# ROBOTICARM.net
KiCad netlist of a schematic drawn in Altium Designer
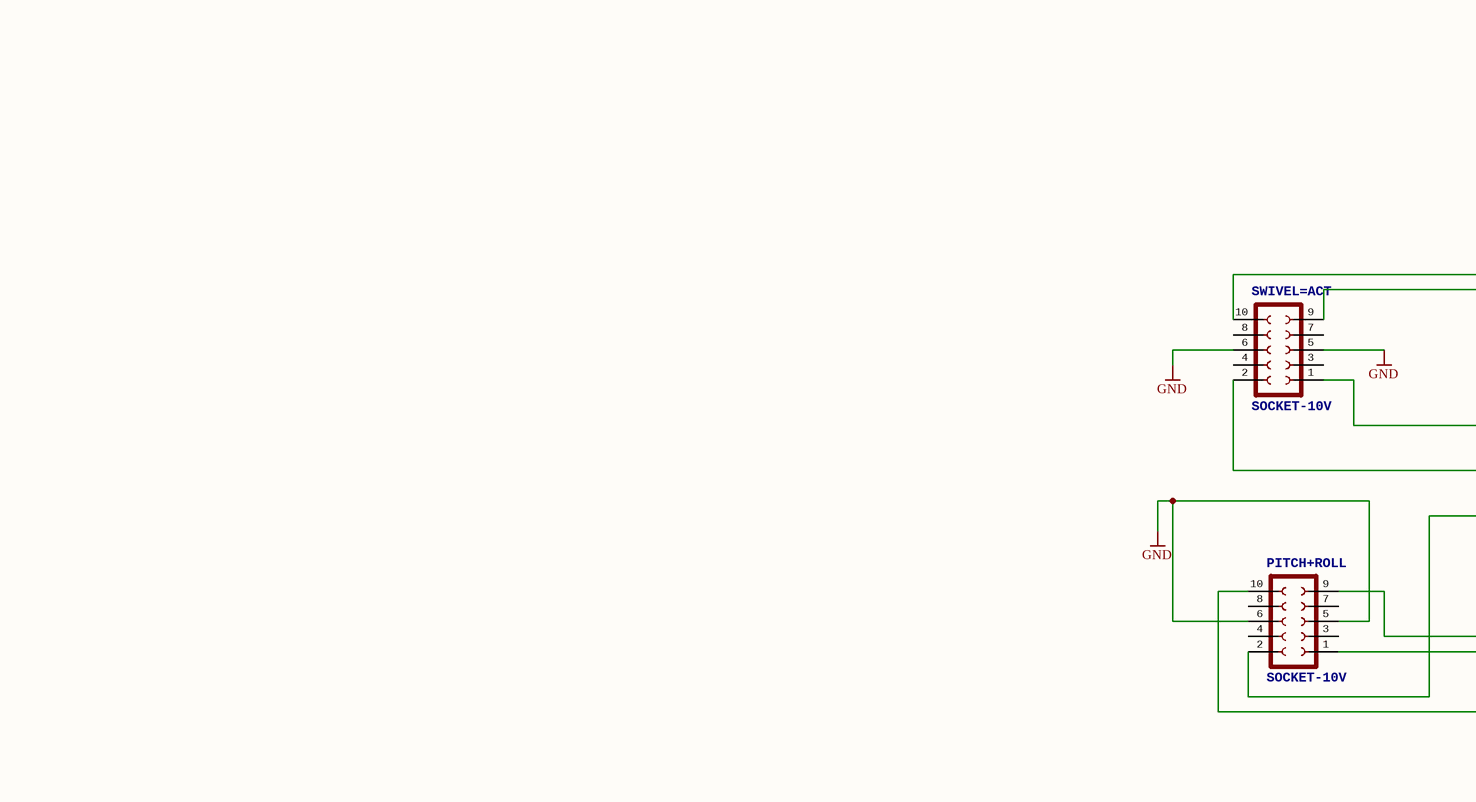
[diagram p0: ROBOTICARM.SchDoc, left]
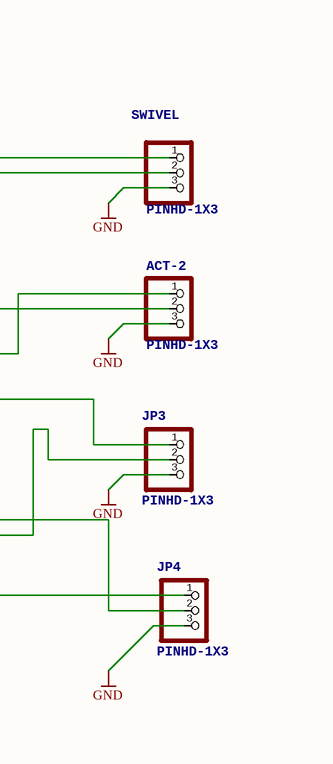
[diagram p1: ROBOTICARM.SchDoc, middle]

(export (version "E")
  (design (tool "Eeschema 10.0.6"))
  (components
    (comp (ref "ACT-2")
      (value "PINHD-1X3")
      (footprint "1X03")
      (description "PIN HEADER")
      (libsource (lib "pinhead") (part "PINHD-1X3"))
    )
    (comp (ref "JP3")
      (value "PINHD-1X3")
      (footprint "1X03")
      (description "PIN HEADER")
      (libsource (lib "pinhead") (part "PINHD-1X3"))
    )
    (comp (ref "JP4")
      (value "PINHD-1X3")
      (footprint "1X03")
      (description "PIN HEADER")
      (libsource (lib "pinhead") (part "PINHD-1X3"))
    )
    (comp (ref "MRM1")
      (value "MRM")
      (footprint "LOL")
      (fields (field (name "MRMLOGO") "MRM Logo"))
      (libsource (lib "MRM") (part "MRM"))
    )
    (comp (ref "PITCH+ROLL")
      (value "SOCKET-10V")
      (footprint "S10V")
      (description "10 pin PCB Socket (3m 85xx/51xx)")
      (libsource (lib "con-3m-skt-header") (part "SOCKET-10V"))
    )
    (comp (ref "SWIVEL")
      (value "PINHD-1X3")
      (footprint "1X03")
      (description "PIN HEADER")
      (libsource (lib "pinhead") (part "PINHD-1X3"))
    )
    (comp (ref "SWIVEL=ACT")
      (value "SOCKET-10V")
      (footprint "S10V")
      (description "10 pin PCB Socket (3m 85xx/51xx)")
      (libsource (lib "con-3m-skt-header") (part "SOCKET-10V"))
    )
  )
  (nets
    (net (code "1") (name "GND") (class "Default")
      (node (ref "ACT-2") (pin "3") (pinfunction "3_3") (pintype "passive"))
      (node (ref "JP3") (pin "3") (pinfunction "3_3") (pintype "passive"))
      (node (ref "JP4") (pin "3") (pinfunction "3_3") (pintype "passive"))
      (node (ref "PITCH+ROLL") (pin "5") (pinfunction "5_5") (pintype "passive"))
      (node (ref "PITCH+ROLL") (pin "6") (pinfunction "6_6") (pintype "passive"))
      (node (ref "SWIVEL") (pin "3") (pinfunction "3_3") (pintype "passive"))
      (node (ref "SWIVEL=ACT") (pin "5") (pinfunction "5_5") (pintype "passive"))
      (node (ref "SWIVEL=ACT") (pin "6") (pinfunction "6_6") (pintype "passive"))
    )
    (net (code "2") (name "Net-(ACT-2-Pad1)") (class "Default")
      (node (ref "ACT-2") (pin "1") (pinfunction "1_1") (pintype "passive"))
      (node (ref "SWIVEL=ACT") (pin "2") (pinfunction "2_2") (pintype "passive"))
    )
    (net (code "3") (name "Net-(ACT-2-Pad2)") (class "Default")
      (node (ref "ACT-2") (pin "2") (pinfunction "2_2") (pintype "passive"))
      (node (ref "SWIVEL=ACT") (pin "1") (pinfunction "1_1") (pintype "passive"))
    )
    (net (code "4") (name "Net-(JP3-Pad1)") (class "Default")
      (node (ref "JP3") (pin "1") (pinfunction "1_1") (pintype "passive"))
      (node (ref "PITCH+ROLL") (pin "2") (pinfunction "2_2") (pintype "passive"))
    )
    (net (code "5") (name "Net-(JP3-Pad2)") (class "Default")
      (node (ref "JP3") (pin "2") (pinfunction "2_2") (pintype "passive"))
      (node (ref "PITCH+ROLL") (pin "1") (pinfunction "1_1") (pintype "passive"))
    )
    (net (code "6") (name "Net-(JP4-Pad1)") (class "Default")
      (node (ref "JP4") (pin "1") (pinfunction "1_1") (pintype "passive"))
      (node (ref "PITCH+ROLL") (pin "10") (pinfunction "10_10") (pintype "passive"))
    )
    (net (code "7") (name "Net-(JP4-Pad2)") (class "Default")
      (node (ref "JP4") (pin "2") (pinfunction "2_2") (pintype "passive"))
      (node (ref "PITCH+ROLL") (pin "9") (pinfunction "9_9") (pintype "passive"))
    )
    (net (code "8") (name "Net-(SWIVEL-Pad1)") (class "Default")
      (node (ref "SWIVEL") (pin "1") (pinfunction "1_1") (pintype "passive"))
      (node (ref "SWIVEL=ACT") (pin "10") (pinfunction "10_10") (pintype "passive"))
    )
    (net (code "9") (name "Net-(SWIVEL-Pad2)") (class "Default")
      (node (ref "SWIVEL") (pin "2") (pinfunction "2_2") (pintype "passive"))
      (node (ref "SWIVEL=ACT") (pin "9") (pinfunction "9_9") (pintype "passive"))
    )
    (net (code "10") (name "unconnected-(PITCH+ROLL-Pad3)") (class "Default")
      (node (ref "PITCH+ROLL") (pin "3") (pinfunction "3_3") (pintype "passive"))
    )
    (net (code "11") (name "unconnected-(PITCH+ROLL-Pad4)") (class "Default")
      (node (ref "PITCH+ROLL") (pin "4") (pinfunction "4_4") (pintype "passive"))
    )
    (net (code "12") (name "unconnected-(PITCH+ROLL-Pad7)") (class "Default")
      (node (ref "PITCH+ROLL") (pin "7") (pinfunction "7_7") (pintype "passive"))
    )
    (net (code "13") (name "unconnected-(PITCH+ROLL-Pad8)") (class "Default")
      (node (ref "PITCH+ROLL") (pin "8") (pinfunction "8_8") (pintype "passive"))
    )
    (net (code "14") (name "unconnected-(SWIVEL=ACT-Pad3)") (class "Default")
      (node (ref "SWIVEL=ACT") (pin "3") (pinfunction "3_3") (pintype "passive"))
    )
    (net (code "15") (name "unconnected-(SWIVEL=ACT-Pad4)") (class "Default")
      (node (ref "SWIVEL=ACT") (pin "4") (pinfunction "4_4") (pintype "passive"))
    )
    (net (code "16") (name "unconnected-(SWIVEL=ACT-Pad7)") (class "Default")
      (node (ref "SWIVEL=ACT") (pin "7") (pinfunction "7_7") (pintype "passive"))
    )
    (net (code "17") (name "unconnected-(SWIVEL=ACT-Pad8)") (class "Default")
      (node (ref "SWIVEL=ACT") (pin "8") (pinfunction "8_8") (pintype "passive"))
    )
  )
)
